# Interface.net
KiCad netlist of a schematic drawn in Altium Designer
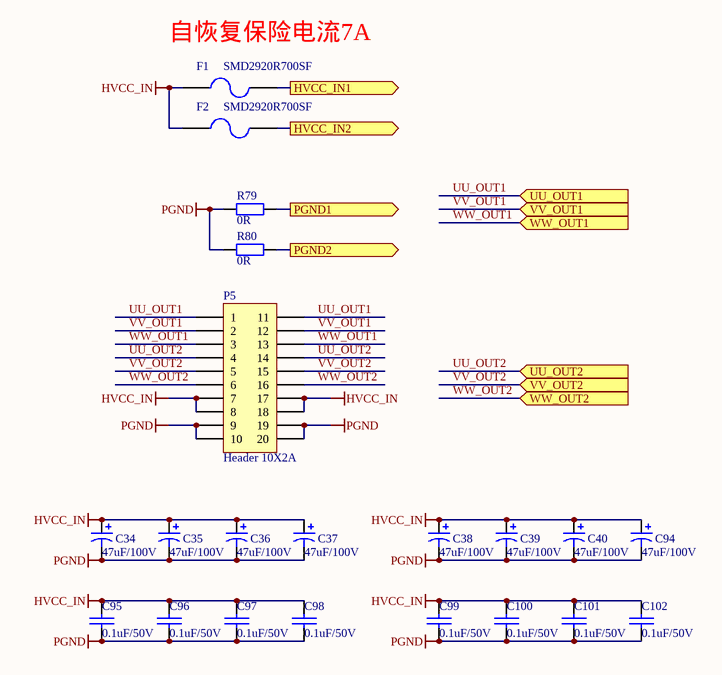
[diagram p0: Interface.SchDoc]

(export (version "E")
  (design (tool "Eeschema 10.0.6"))
  (components
    (comp (ref "C34")
      (value "47uF/100V")
      (footprint "WP_1210CC")
      (description "Polarized Capacitor (Radial)")
      (fields (field (name "PUBLISHER") "Altium Limited"))
      (libsource (lib "Miscellaneous Devices") (part "Cap Pol1"))
    )
    (comp (ref "C35")
      (value "47uF/100V")
      (footprint "WP_1210CC")
      (description "Polarized Capacitor (Radial)")
      (fields (field (name "PUBLISHER") "Altium Limited"))
      (libsource (lib "Miscellaneous Devices") (part "Cap Pol1"))
    )
    (comp (ref "C36")
      (value "47uF/100V")
      (footprint "WP_1210CC")
      (description "Polarized Capacitor (Radial)")
      (fields (field (name "PUBLISHER") "Altium Limited"))
      (libsource (lib "Miscellaneous Devices") (part "Cap Pol1"))
    )
    (comp (ref "C37")
      (value "47uF/100V")
      (footprint "WP_1210CC")
      (description "Polarized Capacitor (Radial)")
      (fields (field (name "PUBLISHER") "Altium Limited"))
      (libsource (lib "Miscellaneous Devices") (part "Cap Pol1"))
    )
    (comp (ref "C38")
      (value "47uF/100V")
      (footprint "WP_1210CC")
      (description "Polarized Capacitor (Radial)")
      (fields (field (name "PUBLISHER") "Altium Limited"))
      (libsource (lib "Miscellaneous Devices") (part "Cap Pol1"))
    )
    (comp (ref "C39")
      (value "47uF/100V")
      (footprint "WP_1210CC")
      (description "Polarized Capacitor (Radial)")
      (fields (field (name "PUBLISHER") "Altium Limited"))
      (libsource (lib "Miscellaneous Devices") (part "Cap Pol1"))
    )
    (comp (ref "C40")
      (value "47uF/100V")
      (footprint "WP_1210CC")
      (description "Polarized Capacitor (Radial)")
      (fields (field (name "PUBLISHER") "Altium Limited"))
      (libsource (lib "Miscellaneous Devices") (part "Cap Pol1"))
    )
    (comp (ref "C94")
      (value "47uF/100V")
      (footprint "WP_1210CC")
      (description "Polarized Capacitor (Radial)")
      (fields (field (name "PUBLISHER") "Altium Limited"))
      (libsource (lib "Miscellaneous Devices") (part "Cap Pol1"))
    )
    (comp (ref "C95")
      (value "0.1uF/50V")
      (footprint "WP_0805C")
      (description "Capacitor")
      (libsource (lib "*") (part "CAP"))
    )
    (comp (ref "C96")
      (value "0.1uF/50V")
      (footprint "WP_0805C")
      (description "Capacitor")
      (libsource (lib "*") (part "CAP"))
    )
    (comp (ref "C97")
      (value "0.1uF/50V")
      (footprint "WP_0805C")
      (description "Capacitor")
      (libsource (lib "*") (part "CAP"))
    )
    (comp (ref "C98")
      (value "0.1uF/50V")
      (footprint "WP_0805C")
      (description "Capacitor")
      (libsource (lib "*") (part "CAP"))
    )
    (comp (ref "C99")
      (value "0.1uF/50V")
      (footprint "WP_0805C")
      (description "Capacitor")
      (libsource (lib "*") (part "CAP"))
    )
    (comp (ref "C100")
      (value "0.1uF/50V")
      (footprint "WP_0805C")
      (description "Capacitor")
      (libsource (lib "*") (part "CAP"))
    )
    (comp (ref "C101")
      (value "0.1uF/50V")
      (footprint "WP_0805C")
      (description "Capacitor")
      (libsource (lib "*") (part "CAP"))
    )
    (comp (ref "C102")
      (value "0.1uF/50V")
      (footprint "WP_0805C")
      (description "Capacitor")
      (libsource (lib "*") (part "CAP"))
    )
    (comp (ref "F1")
      (value "SMD2920R700SF")
      (footprint "WP_2420")
      (description "Fuse")
      (fields (field (name "PUBLISHER") "Altium Limited"))
      (libsource (lib "Miscellaneous Devices") (part "Fuse 2"))
    )
    (comp (ref "F2")
      (value "SMD2920R700SF")
      (footprint "WP_2420")
      (description "Fuse")
      (fields (field (name "PUBLISHER") "Altium Limited"))
      (libsource (lib "Miscellaneous Devices") (part "Fuse 2"))
    )
    (comp (ref "P5")
      (value "Header 10X2A")
      (footprint "WP_CRM222-020")
      (description "Header, 10-Pin, Dual row")
      (fields (field (name "PUBLISHER") "Altium Limited"))
      (libsource (lib "Miscellaneous Connectors") (part "Header 10X2A"))
    )
    (comp (ref "R79")
      (value "0R")
      (footprint "WP_JS2L")
      (description "Resistor")
      (fields (field (name "PUBLISHER") "Altium Limited"))
      (libsource (lib "*") (part "Res2"))
    )
    (comp (ref "R80")
      (value "0R")
      (footprint "WP_JS2L")
      (description "Resistor")
      (fields (field (name "PUBLISHER") "Altium Limited"))
      (libsource (lib "*") (part "Res2"))
    )
  )
  (nets
    (net (code "1") (name "/HVCC_IN1") (class "Default")
      (node (ref "F1") (pin "2") (pinfunction "2_2") (pintype "passive"))
    )
    (net (code "2") (name "/HVCC_IN2") (class "Default")
      (node (ref "F2") (pin "2") (pinfunction "2_2") (pintype "passive"))
    )
    (net (code "3") (name "/PGND1") (class "Default")
      (node (ref "R79") (pin "2") (pinfunction "2_2") (pintype "passive"))
    )
    (net (code "4") (name "/PGND2") (class "Default")
      (node (ref "R80") (pin "2") (pinfunction "2_2") (pintype "passive"))
    )
    (net (code "5") (name "/UU_OUT1") (class "Default")
      (node (ref "P5") (pin "1") (pinfunction "1_1") (pintype "passive"))
      (node (ref "P5") (pin "11") (pinfunction "11_11") (pintype "passive"))
    )
    (net (code "6") (name "/UU_OUT2") (class "Default")
      (node (ref "P5") (pin "14") (pinfunction "14_14") (pintype "passive"))
      (node (ref "P5") (pin "4") (pinfunction "4_4") (pintype "passive"))
    )
    (net (code "7") (name "/VV_OUT1") (class "Default")
      (node (ref "P5") (pin "12") (pinfunction "12_12") (pintype "passive"))
      (node (ref "P5") (pin "2") (pinfunction "2_2") (pintype "passive"))
    )
    (net (code "8") (name "/VV_OUT2") (class "Default")
      (node (ref "P5") (pin "15") (pinfunction "15_15") (pintype "passive"))
      (node (ref "P5") (pin "5") (pinfunction "5_5") (pintype "passive"))
    )
    (net (code "9") (name "/WW_OUT1") (class "Default")
      (node (ref "P5") (pin "13") (pinfunction "13_13") (pintype "passive"))
      (node (ref "P5") (pin "3") (pinfunction "3_3") (pintype "passive"))
    )
    (net (code "10") (name "/WW_OUT2") (class "Default")
      (node (ref "P5") (pin "16") (pinfunction "16_16") (pintype "passive"))
      (node (ref "P5") (pin "6") (pinfunction "6_6") (pintype "passive"))
    )
    (net (code "12") (name "HVCC_IN") (class "Default")
      (node (ref "C100") (pin "1") (pinfunction "1_1") (pintype "passive"))
      (node (ref "C101") (pin "1") (pinfunction "1_1") (pintype "passive"))
      (node (ref "C102") (pin "1") (pinfunction "1_1") (pintype "passive"))
      (node (ref "C34") (pin "1") (pinfunction "1_1") (pintype "passive"))
      (node (ref "C35") (pin "1") (pinfunction "1_1") (pintype "passive"))
      (node (ref "C36") (pin "1") (pinfunction "1_1") (pintype "passive"))
      (node (ref "C37") (pin "1") (pinfunction "1_1") (pintype "passive"))
      (node (ref "C38") (pin "1") (pinfunction "1_1") (pintype "passive"))
      (node (ref "C39") (pin "1") (pinfunction "1_1") (pintype "passive"))
      (node (ref "C40") (pin "1") (pinfunction "1_1") (pintype "passive"))
      (node (ref "C94") (pin "1") (pinfunction "1_1") (pintype "passive"))
      (node (ref "C95") (pin "1") (pinfunction "1_1") (pintype "passive"))
      (node (ref "C96") (pin "1") (pinfunction "1_1") (pintype "passive"))
      (node (ref "C97") (pin "1") (pinfunction "1_1") (pintype "passive"))
      (node (ref "C98") (pin "1") (pinfunction "1_1") (pintype "passive"))
      (node (ref "C99") (pin "1") (pinfunction "1_1") (pintype "passive"))
      (node (ref "F1") (pin "1") (pinfunction "1_1") (pintype "passive"))
      (node (ref "F2") (pin "1") (pinfunction "1_1") (pintype "passive"))
      (node (ref "P5") (pin "17") (pinfunction "17_17") (pintype "passive"))
      (node (ref "P5") (pin "18") (pinfunction "18_18") (pintype "passive"))
      (node (ref "P5") (pin "7") (pinfunction "7_7") (pintype "passive"))
      (node (ref "P5") (pin "8") (pinfunction "8_8") (pintype "passive"))
    )
    (net (code "13") (name "PGND") (class "Default")
      (node (ref "C100") (pin "2") (pinfunction "2_2") (pintype "passive"))
      (node (ref "C101") (pin "2") (pinfunction "2_2") (pintype "passive"))
      (node (ref "C102") (pin "2") (pinfunction "2_2") (pintype "passive"))
      (node (ref "C34") (pin "2") (pinfunction "2_2") (pintype "passive"))
      (node (ref "C35") (pin "2") (pinfunction "2_2") (pintype "passive"))
      (node (ref "C36") (pin "2") (pinfunction "2_2") (pintype "passive"))
      (node (ref "C37") (pin "2") (pinfunction "2_2") (pintype "passive"))
      (node (ref "C38") (pin "2") (pinfunction "2_2") (pintype "passive"))
      (node (ref "C39") (pin "2") (pinfunction "2_2") (pintype "passive"))
      (node (ref "C40") (pin "2") (pinfunction "2_2") (pintype "passive"))
      (node (ref "C94") (pin "2") (pinfunction "2_2") (pintype "passive"))
      (node (ref "C95") (pin "2") (pinfunction "2_2") (pintype "passive"))
      (node (ref "C96") (pin "2") (pinfunction "2_2") (pintype "passive"))
      (node (ref "C97") (pin "2") (pinfunction "2_2") (pintype "passive"))
      (node (ref "C98") (pin "2") (pinfunction "2_2") (pintype "passive"))
      (node (ref "C99") (pin "2") (pinfunction "2_2") (pintype "passive"))
      (node (ref "P5") (pin "10") (pinfunction "10_10") (pintype "passive"))
      (node (ref "P5") (pin "19") (pinfunction "19_19") (pintype "passive"))
      (node (ref "P5") (pin "20") (pinfunction "20_20") (pintype "passive"))
      (node (ref "P5") (pin "9") (pinfunction "9_9") (pintype "passive"))
      (node (ref "R79") (pin "1") (pinfunction "1_1") (pintype "passive"))
      (node (ref "R80") (pin "1") (pinfunction "1_1") (pintype "passive"))
    )
  )
)
